# DM1098OAKW_LEFT_OV9282.net
KiCad netlist of a schematic drawn in Altium Designer
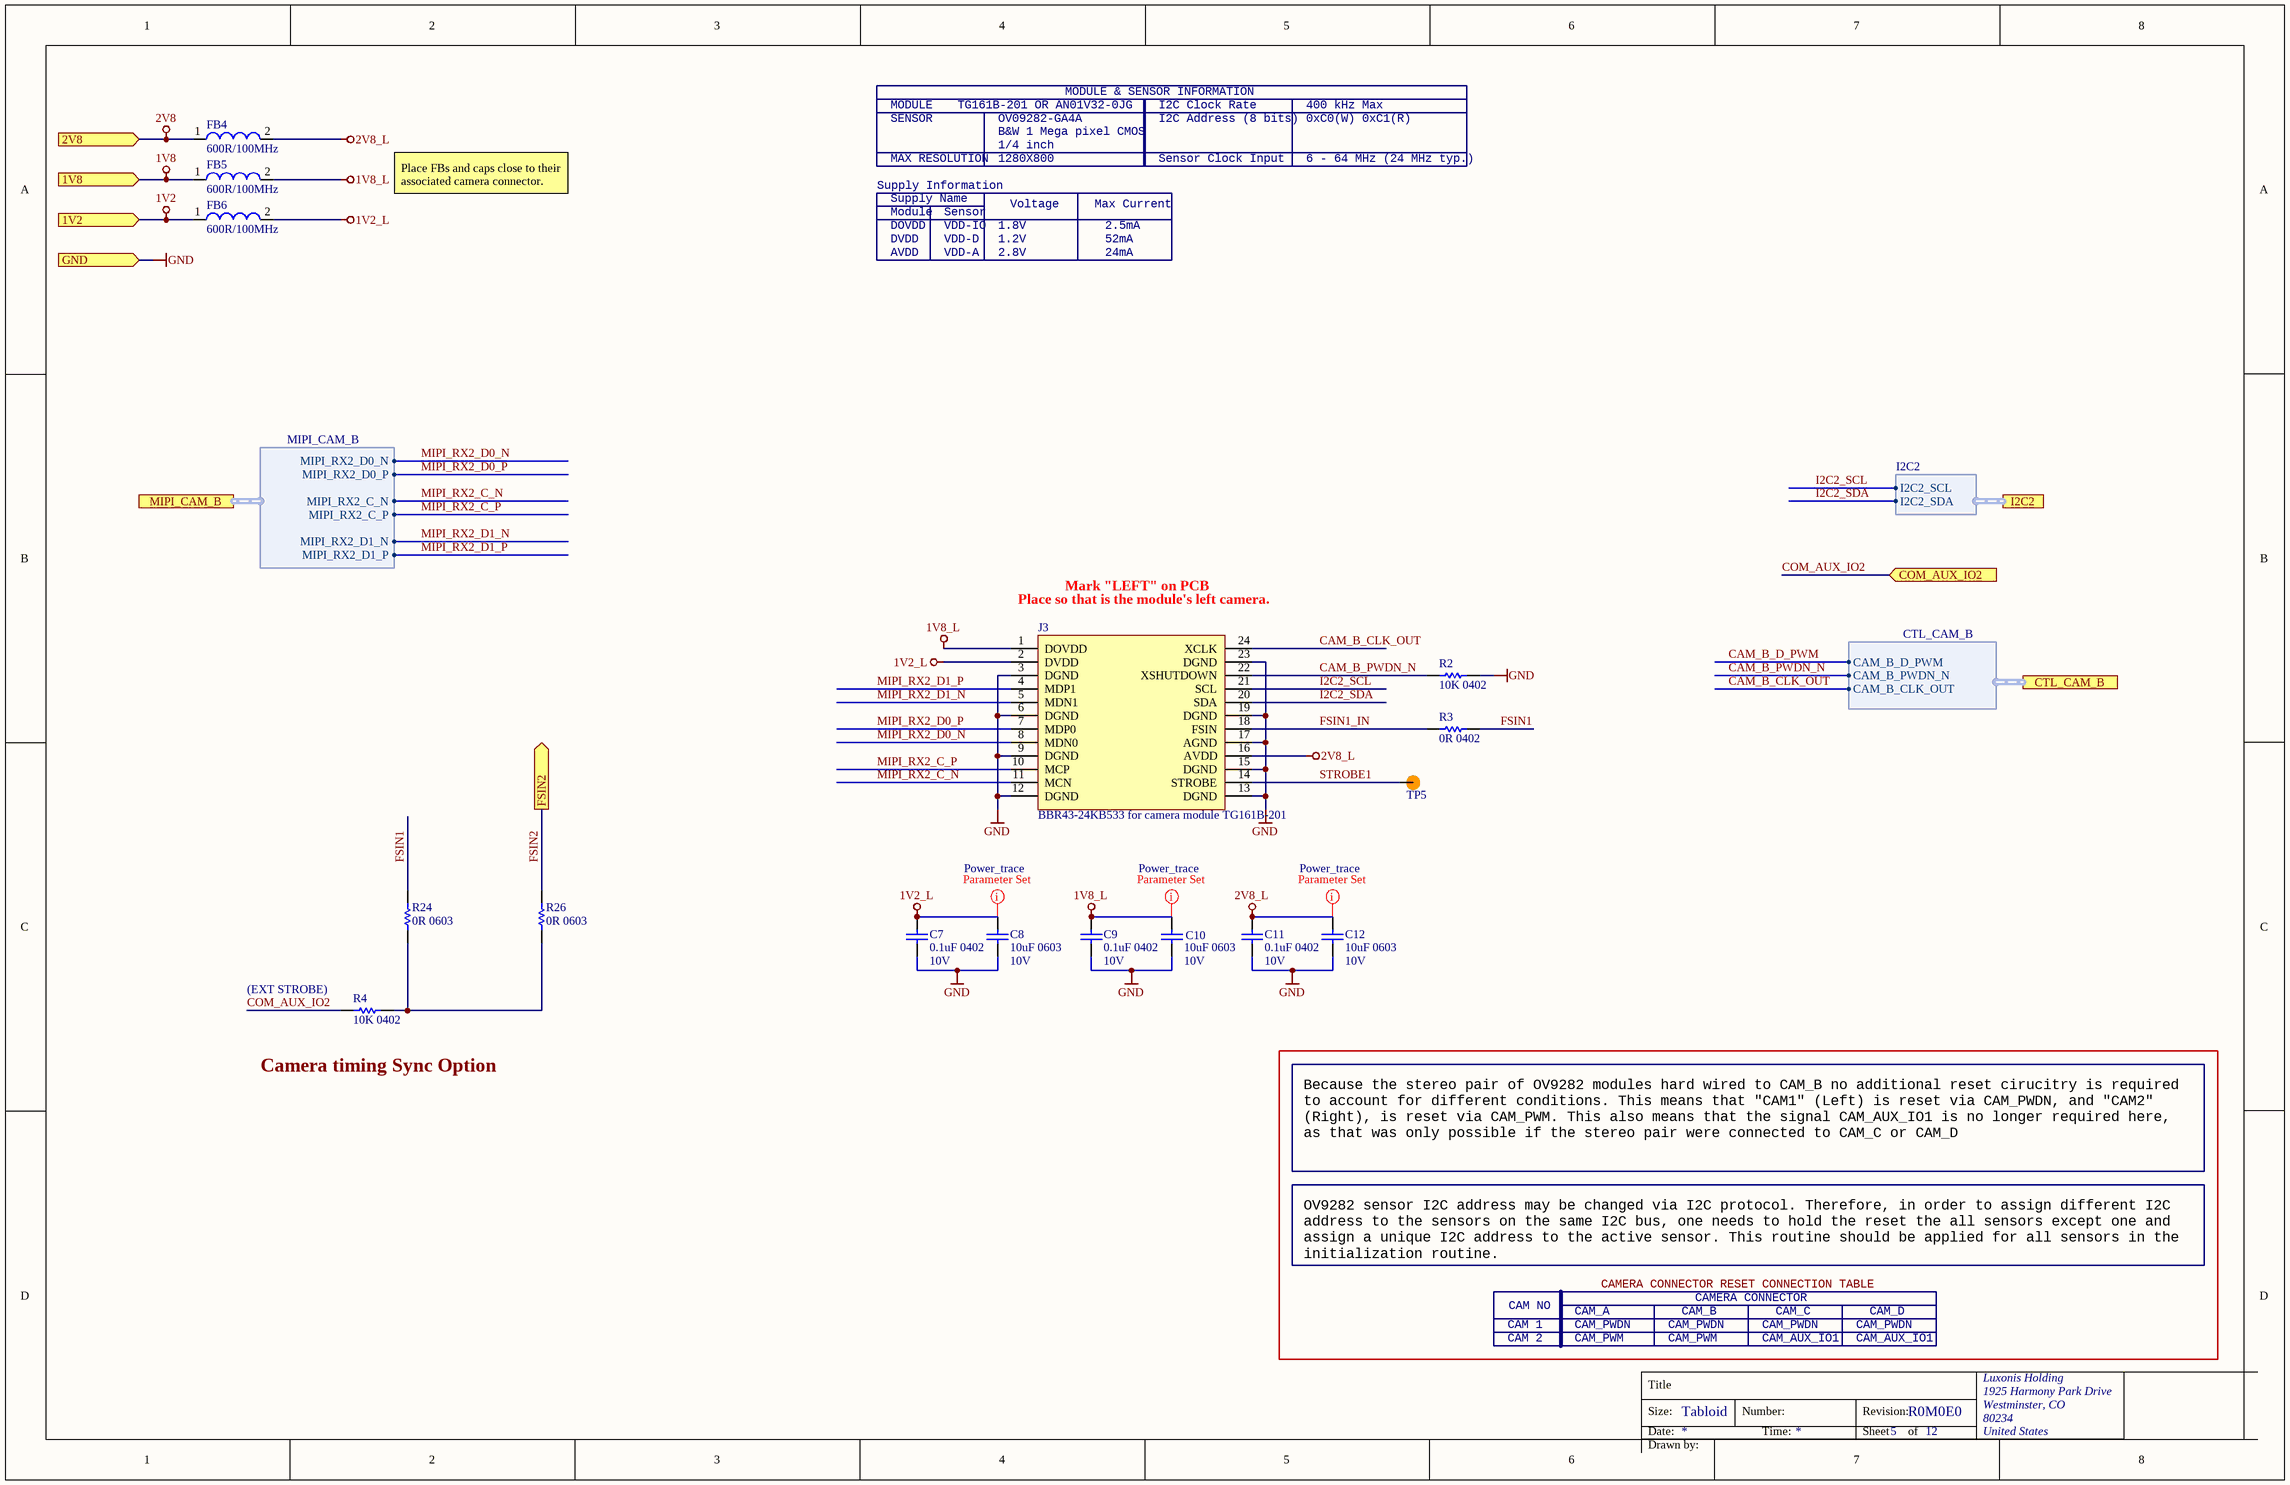
[diagram p0: DM1098OAKW_LEFT_OV9282.SchDoc]

(export (version "E")
  (design (tool "Eeschema 10.0.6"))
  (components
    (comp (ref "C7")
      (value "0.1uF 0402")
      (footprint "CAP_Altium_Vault_Generic:CAPC0402(1005)70_L")
      (description "CAP CER 0.1UF 10V X7R 0402 5%")
      (fields (field (name "TOLERANCE") "5%") (field (name "VOLTAGE RATING") "10V"))
      (libsource (lib "LuxonisMaster") (part "GRM155R71A104JA01D"))
    )
    (comp (ref "C8")
      (value "10uF 0603")
      (footprint "CAP_Altium_Vault_Generic:CAPC0603(1608)100_L")
      (description "CAP CER 10UF 10V X5R 0603 20%")
      (fields (field (name "TOLERANCE") "20%") (field (name "VOLTAGE RATING") "10V"))
      (libsource (lib "LuxonisMaster") (part "GRM188R61A106ME69D"))
    )
    (comp (ref "C9")
      (value "0.1uF 0402")
      (footprint "CAP_Altium_Vault_Generic:CAPC0402(1005)70_L")
      (description "CAP CER 0.1UF 10V X7R 0402 5%")
      (fields (field (name "TOLERANCE") "5%") (field (name "VOLTAGE RATING") "10V"))
      (libsource (lib "LuxonisMaster") (part "GRM155R71A104JA01D"))
    )
    (comp (ref "C10")
      (value "10uF 0603")
      (footprint "CAP_Altium_Vault_Generic:CAPC0603(1608)100_L")
      (description "CAP CER 10UF 10V X5R 0603 20%")
      (fields (field (name "TOLERANCE") "20%") (field (name "VOLTAGE RATING") "10V"))
      (libsource (lib "LuxonisMaster") (part "GRM188R61A106ME69D"))
    )
    (comp (ref "C11")
      (value "0.1uF 0402")
      (footprint "CAP_Altium_Vault_Generic:CAPC0402(1005)70_L")
      (description "CAP CER 0.1UF 10V X7R 0402 5%")
      (fields (field (name "TOLERANCE") "5%") (field (name "VOLTAGE RATING") "10V"))
      (libsource (lib "LuxonisMaster") (part "GRM155R71A104JA01D"))
    )
    (comp (ref "C12")
      (value "10uF 0603")
      (footprint "CAP_Altium_Vault_Generic:CAPC0603(1608)100_L")
      (description "CAP CER 10UF 10V X5R 0603 20%")
      (fields (field (name "TOLERANCE") "20%") (field (name "VOLTAGE RATING") "10V"))
      (libsource (lib "LuxonisMaster") (part "GRM188R61A106ME69D"))
    )
    (comp (ref "FB4")
      (value "600R/100MHz")
      (footprint "LuxonisMaster:2508056017Y2")
      (description "FERRITE BEAD, 0.1OHM, 2A, 0805, 600R/100MHz")
      (fields (field (name "TOLERANCE") "25%"))
      (libsource (lib "LuxonisMaster") (part "2508056017Y2"))
    )
    (comp (ref "FB5")
      (value "600R/100MHz")
      (footprint "LuxonisMaster:2508056017Y2")
      (description "FERRITE BEAD, 0.1OHM, 2A, 0805, 600R/100MHz")
      (fields (field (name "TOLERANCE") "25%"))
      (libsource (lib "LuxonisMaster") (part "2508056017Y2"))
    )
    (comp (ref "FB6")
      (value "600R/100MHz")
      (footprint "LuxonisMaster:2508056017Y2")
      (description "FERRITE BEAD, 0.1OHM, 2A, 0805, 600R/100MHz")
      (fields (field (name "TOLERANCE") "25%"))
      (libsource (lib "LuxonisMaster") (part "2508056017Y2"))
    )
    (comp (ref "J3")
      (value "BBR43-24KB533 for camera module TG161B-201")
      (footprint "LuxonisMaster:TG161B-201")
      (description "CONN 24 way, 2 row board to board connector SMD")
      (libsource (lib "LuxonisMaster") (part "TG161B-201_Connector"))
    )
    (comp (ref "R2")
      (value "10K 0402")
      (footprint "RES_Altium_Vault_Generic:RESC0402(1005)_L")
      (fields (field (name "TOLERANCE") "1%"))
      (libsource (lib "LuxonisMaster") (part "RC0402FR-1310KL"))
    )
    (comp (ref "R3")
      (value "0R 0402")
      (footprint "RES_Altium_Vault_Generic:RESC0402(1005)_L")
      (description "RES SMD 0 OHM JUMPER 1/16W 0402")
      (fields (field (name "TOLERANCE") "5%"))
      (libsource (lib "LuxonisMaster") (part "CRCW04020000Z0ED"))
    )
    (comp (ref "R4")
      (value "10K 0402")
      (footprint "RES_Altium_Vault_Generic:RESC0402(1005)_L")
      (fields (field (name "TOLERANCE") "1%"))
      (libsource (lib "LuxonisMaster") (part "RC0402FR-1310KL"))
    )
    (comp (ref "R24")
      (value "0R 0603")
      (footprint "RES_Altium_Vault_Generic:RESC0603(1608)_N")
      (fields (field (name "TOLERANCE") "5%"))
      (libsource (lib "LuxonisMaster") (part "CRCW06030000Z0EA"))
    )
    (comp (ref "R26")
      (value "0R 0603")
      (footprint "RES_Altium_Vault_Generic:RESC0603(1608)_N")
      (fields (field (name "TOLERANCE") "5%"))
      (libsource (lib "LuxonisMaster") (part "CRCW06030000Z0EA"))
    )
    (comp (ref "TP5")
      (value "TP100_200_NS")
      (footprint "LuxonisMaster:TP100_200_NS")
      (libsource (lib "LuxonisMaster") (part "TEST_POINT"))
    )
  )
  (nets
    (net (code "4") (name "/CAM_B_CLK_OUT") (class "Default")
      (node (ref "J3") (pin "24") (pinfunction "XCLK_24") (pintype "passive"))
    )
    (net (code "6") (name "/CAM_B_PWDN_N") (class "Default")
      (node (ref "J3") (pin "22") (pinfunction "XSHUTDOWN_22") (pintype "passive"))
      (node (ref "R2") (pin "1") (pinfunction "1_1") (pintype "passive"))
    )
    (net (code "7") (name "/COM_AUX_IO2") (class "Default")
      (node (ref "R4") (pin "1") (pinfunction "1_1") (pintype "passive"))
    )
    (net (code "8") (name "/FSIN1") (class "Default")
      (node (ref "R24") (pin "2") (pinfunction "2_2") (pintype "passive"))
      (node (ref "R3") (pin "2") (pinfunction "2_2") (pintype "passive"))
    )
    (net (code "9") (name "/FSIN1_IN") (class "Default")
      (node (ref "J3") (pin "18") (pinfunction "FSIN_18") (pintype "passive"))
      (node (ref "R3") (pin "1") (pinfunction "1_1") (pintype "passive"))
    )
    (net (code "10") (name "/FSIN2") (class "Default")
      (node (ref "R26") (pin "2") (pinfunction "2_2") (pintype "passive"))
    )
    (net (code "11") (name "/I2C2_SCL") (class "Default")
      (node (ref "J3") (pin "21") (pinfunction "SCL_21") (pintype "passive"))
    )
    (net (code "12") (name "/I2C2_SDA") (class "Default")
      (node (ref "J3") (pin "20") (pinfunction "SDA_20") (pintype "passive"))
    )
    (net (code "13") (name "/MIPI_RX2_C_N") (class "Default")
      (node (ref "J3") (pin "11") (pinfunction "MCN_11") (pintype "passive"))
    )
    (net (code "14") (name "/MIPI_RX2_C_P") (class "Default")
      (node (ref "J3") (pin "10") (pinfunction "MCP_10") (pintype "passive"))
    )
    (net (code "15") (name "/MIPI_RX2_D0_N") (class "Default")
      (node (ref "J3") (pin "8") (pinfunction "MDN0_8") (pintype "passive"))
    )
    (net (code "16") (name "/MIPI_RX2_D0_P") (class "Default")
      (node (ref "J3") (pin "7") (pinfunction "MDP0_7") (pintype "passive"))
    )
    (net (code "17") (name "/MIPI_RX2_D1_N") (class "Default")
      (node (ref "J3") (pin "5") (pinfunction "MDN1_5") (pintype "passive"))
    )
    (net (code "18") (name "/MIPI_RX2_D1_P") (class "Default")
      (node (ref "J3") (pin "4") (pinfunction "MDP1_4") (pintype "passive"))
    )
    (net (code "19") (name "/STROBE1") (class "Default")
      (node (ref "J3") (pin "14") (pinfunction "STROBE_14") (pintype "passive"))
      (node (ref "TP5") (pin "1") (pintype "passive"))
    )
    (net (code "23") (name "1V2") (class "Default")
      (node (ref "FB6") (pin "1") (pinfunction "1_1") (pintype "passive"))
    )
    (net (code "24") (name "1V2_L") (class "Default")
      (node (ref "C7") (pin "2") (pinfunction "2_2") (pintype "passive"))
      (node (ref "C8") (pin "2") (pinfunction "2_2") (pintype "passive"))
      (node (ref "FB6") (pin "2") (pinfunction "2_2") (pintype "passive"))
      (node (ref "J3") (pin "2") (pinfunction "DVDD_2") (pintype "passive"))
    )
    (net (code "25") (name "1V8") (class "Default")
      (node (ref "FB5") (pin "1") (pinfunction "1_1") (pintype "passive"))
    )
    (net (code "26") (name "1V8_L") (class "Default")
      (node (ref "C10") (pin "2") (pinfunction "2_2") (pintype "passive"))
      (node (ref "C9") (pin "2") (pinfunction "2_2") (pintype "passive"))
      (node (ref "FB5") (pin "2") (pinfunction "2_2") (pintype "passive"))
      (node (ref "J3") (pin "1") (pinfunction "DOVDD_1") (pintype "passive"))
    )
    (net (code "27") (name "2V8") (class "Default")
      (node (ref "FB4") (pin "1") (pinfunction "1_1") (pintype "passive"))
    )
    (net (code "28") (name "2V8_L") (class "Default")
      (node (ref "C11") (pin "2") (pinfunction "2_2") (pintype "passive"))
      (node (ref "C12") (pin "2") (pinfunction "2_2") (pintype "passive"))
      (node (ref "FB4") (pin "2") (pinfunction "2_2") (pintype "passive"))
      (node (ref "J3") (pin "16") (pinfunction "AVDD_16") (pintype "passive"))
    )
    (net (code "29") (name "GND") (class "Default")
      (node (ref "C10") (pin "1") (pinfunction "1_1") (pintype "passive"))
      (node (ref "C11") (pin "1") (pinfunction "1_1") (pintype "passive"))
      (node (ref "C12") (pin "1") (pinfunction "1_1") (pintype "passive"))
      (node (ref "C7") (pin "1") (pinfunction "1_1") (pintype "passive"))
      (node (ref "C8") (pin "1") (pinfunction "1_1") (pintype "passive"))
      (node (ref "C9") (pin "1") (pinfunction "1_1") (pintype "passive"))
      (node (ref "J3") (pin "12") (pinfunction "DGND_12") (pintype "passive"))
      (node (ref "J3") (pin "13") (pinfunction "DGND_13") (pintype "passive"))
      (node (ref "J3") (pin "15") (pinfunction "DGND_15") (pintype "passive"))
      (node (ref "J3") (pin "17") (pinfunction "AGND_17") (pintype "passive"))
      (node (ref "J3") (pin "19") (pinfunction "DGND_19") (pintype "passive"))
      (node (ref "J3") (pin "23") (pinfunction "DGND_23") (pintype "passive"))
      (node (ref "J3") (pin "3") (pinfunction "DGND_3") (pintype "passive"))
      (node (ref "J3") (pin "6") (pinfunction "DGND_6") (pintype "passive"))
      (node (ref "J3") (pin "9") (pinfunction "DGND_9") (pintype "passive"))
      (node (ref "R2") (pin "2") (pinfunction "2_2") (pintype "passive"))
    )
    (net (code "30") (name "Net-(R24-Pad1)") (class "Default")
      (node (ref "R24") (pin "1") (pinfunction "1_1") (pintype "passive"))
      (node (ref "R26") (pin "1") (pinfunction "1_1") (pintype "passive"))
      (node (ref "R4") (pin "2") (pinfunction "2_2") (pintype "passive"))
    )
  )
)
